# Capstone.net
KiCad netlist of a schematic drawn in EAGLE
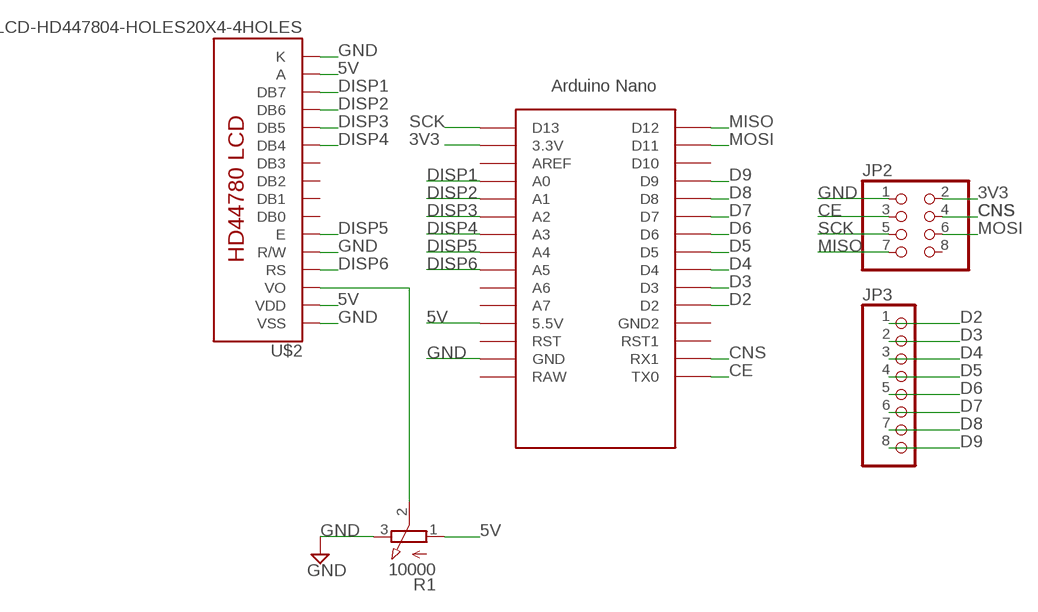
[diagram p0: schematic, sheet 1]

(export (version "E")
  (design (tool "Eeschema 10.0.6"))
  (components
    (comp (ref "JP2")
      (value "PINHD-2X4")
      (footprint "eagle-import:2X04")
      (libsource (lib "eagle-import") (part "PINHD-2X4"))
    )
    (comp (ref "JP3")
      (value "PINHD-1X8")
      (footprint "eagle-import:1X08")
      (libsource (lib "eagle-import") (part "PINHD-1X8"))
    )
    (comp (ref "R1")
      (value "10000")
      (footprint "eagle-import:3RP_1610N")
      (libsource (lib "eagle-import") (part "3RP/1610N"))
    )
    (comp (ref "U$1")
      (value "NANO")
      (footprint "eagle-import:NANO")
      (libsource (lib "eagle-import") (part "NANO"))
    )
    (comp (ref "U$2")
      (value "LCD-HD447804-HOLES20X4-4HOLES")
      (footprint "eagle-import:LCD-20X4-4HOLES")
      (libsource (lib "eagle-import") (part "LCD-HD4478020X4-4HOLES4-HOLES"))
    )
  )
  (nets
    (net (code "1") (name "/3V3") (class "Default")
      (node (ref "JP2") (pin "2") (pinfunction "2_2") (pintype "passive"))
      (node (ref "U$1") (pin "3.3V") (pinfunction "3.3V_3.3V") (pintype "bidirectional"))
    )
    (net (code "2") (name "/5V") (class "Default")
      (node (ref "R1") (pin "1") (pinfunction "A_1") (pintype "passive"))
      (node (ref "U$1") (pin "5V") (pinfunction "5.5V_5V") (pintype "bidirectional"))
      (node (ref "U$2") (pin "P$15") (pinfunction "A_P$15") (pintype "power_in"))
      (node (ref "U$2") (pin "P$2") (pinfunction "VDD_P$2") (pintype "power_in"))
    )
    (net (code "3") (name "/CE") (class "Default")
      (node (ref "JP2") (pin "3") (pinfunction "3_3") (pintype "passive"))
      (node (ref "U$1") (pin "TX0") (pinfunction "TX0_TX0") (pintype "bidirectional"))
    )
    (net (code "4") (name "/CNS") (class "Default")
      (node (ref "JP2") (pin "4") (pinfunction "4_4") (pintype "passive"))
      (node (ref "U$1") (pin "RX1") (pinfunction "RX1_RX1") (pintype "bidirectional"))
    )
    (net (code "5") (name "/D2") (class "Default")
      (node (ref "JP3") (pin "1") (pinfunction "1_1") (pintype "passive"))
      (node (ref "U$1") (pin "D2") (pinfunction "D2_D2") (pintype "bidirectional"))
    )
    (net (code "6") (name "/D3") (class "Default")
      (node (ref "JP3") (pin "2") (pinfunction "2_2") (pintype "passive"))
      (node (ref "U$1") (pin "D3") (pinfunction "D3_D3") (pintype "bidirectional"))
    )
    (net (code "7") (name "/D4") (class "Default")
      (node (ref "JP3") (pin "3") (pinfunction "3_3") (pintype "passive"))
      (node (ref "U$1") (pin "D4") (pinfunction "D4_D4") (pintype "bidirectional"))
    )
    (net (code "8") (name "/D5") (class "Default")
      (node (ref "JP3") (pin "4") (pinfunction "4_4") (pintype "passive"))
      (node (ref "U$1") (pin "D5") (pinfunction "D5_D5") (pintype "bidirectional"))
    )
    (net (code "9") (name "/D6") (class "Default")
      (node (ref "JP3") (pin "5") (pinfunction "5_5") (pintype "passive"))
      (node (ref "U$1") (pin "D6") (pinfunction "D6_D6") (pintype "bidirectional"))
    )
    (net (code "10") (name "/D7") (class "Default")
      (node (ref "JP3") (pin "6") (pinfunction "6_6") (pintype "passive"))
      (node (ref "U$1") (pin "D7") (pinfunction "D7_D7") (pintype "bidirectional"))
    )
    (net (code "11") (name "/D8") (class "Default")
      (node (ref "JP3") (pin "7") (pinfunction "7_7") (pintype "passive"))
      (node (ref "U$1") (pin "D8") (pinfunction "D8_D8") (pintype "bidirectional"))
    )
    (net (code "12") (name "/D9") (class "Default")
      (node (ref "JP3") (pin "8") (pinfunction "8_8") (pintype "passive"))
      (node (ref "U$1") (pin "D9") (pinfunction "D9_D9") (pintype "bidirectional"))
    )
    (net (code "13") (name "/DISP1") (class "Default")
      (node (ref "U$1") (pin "A0") (pinfunction "A0_A0") (pintype "bidirectional"))
      (node (ref "U$2") (pin "P$14") (pinfunction "DB7_P$14") (pintype "bidirectional"))
    )
    (net (code "14") (name "/DISP2") (class "Default")
      (node (ref "U$1") (pin "A1") (pinfunction "A1_A1") (pintype "bidirectional"))
      (node (ref "U$2") (pin "P$13") (pinfunction "DB6_P$13") (pintype "bidirectional"))
    )
    (net (code "15") (name "/DISP3") (class "Default")
      (node (ref "U$1") (pin "A2") (pinfunction "A2_A2") (pintype "bidirectional"))
      (node (ref "U$2") (pin "P$12") (pinfunction "DB5_P$12") (pintype "bidirectional"))
    )
    (net (code "16") (name "/DISP4") (class "Default")
      (node (ref "U$1") (pin "A3") (pinfunction "A3_A3") (pintype "bidirectional"))
      (node (ref "U$2") (pin "P$11") (pinfunction "DB4_P$11") (pintype "bidirectional"))
    )
    (net (code "17") (name "/DISP5") (class "Default")
      (node (ref "U$1") (pin "A4") (pinfunction "A4_A4") (pintype "bidirectional"))
      (node (ref "U$2") (pin "P$6") (pinfunction "E_P$6") (pintype "input"))
    )
    (net (code "18") (name "/DISP6") (class "Default")
      (node (ref "U$1") (pin "A5") (pinfunction "A5_A5") (pintype "bidirectional"))
      (node (ref "U$2") (pin "P$4") (pinfunction "RS_P$4") (pintype "input"))
    )
    (net (code "19") (name "/MISO") (class "Default")
      (node (ref "JP2") (pin "7") (pinfunction "7_7") (pintype "passive"))
      (node (ref "U$1") (pin "D12") (pinfunction "D12_D12") (pintype "bidirectional"))
    )
    (net (code "20") (name "/MOSI") (class "Default")
      (node (ref "JP2") (pin "6") (pinfunction "6_6") (pintype "passive"))
      (node (ref "U$1") (pin "D11") (pinfunction "D11_D11") (pintype "bidirectional"))
    )
    (net (code "21") (name "/SCK") (class "Default")
      (node (ref "JP2") (pin "5") (pinfunction "5_5") (pintype "passive"))
      (node (ref "U$1") (pin "D13") (pinfunction "D13_D13") (pintype "bidirectional"))
    )
    (net (code "22") (name "GND") (class "Default")
      (node (ref "JP2") (pin "1") (pinfunction "1_1") (pintype "passive"))
      (node (ref "R1") (pin "3") (pinfunction "E_3") (pintype "passive"))
      (node (ref "U$1") (pin "GND") (pinfunction "GND_GND") (pintype "bidirectional"))
      (node (ref "U$2") (pin "P$1") (pinfunction "VSS_P$1") (pintype "power_in"))
      (node (ref "U$2") (pin "P$16") (pinfunction "K_P$16") (pintype "power_in"))
      (node (ref "U$2") (pin "P$5") (pinfunction "R/W_P$5") (pintype "input"))
    )
    (net (code "23") (name "Net-(R1-S)") (class "Default")
      (node (ref "R1") (pin "2") (pinfunction "S_2") (pintype "passive"))
      (node (ref "U$2") (pin "P$3") (pinfunction "VO_P$3") (pintype "bidirectional"))
    )
    (net (code "24") (name "unconnected-(JP2-Pad8)") (class "Default")
      (node (ref "JP2") (pin "8") (pinfunction "8_8") (pintype "passive"))
    )
    (net (code "25") (name "unconnected-(U$1-GND2-PadGND1)") (class "Default")
      (node (ref "U$1") (pin "GND1") (pinfunction "GND2_GND1") (pintype "bidirectional"))
    )
    (net (code "26") (name "unconnected-(U$1-PadA6)") (class "Default")
      (node (ref "U$1") (pin "A6") (pinfunction "A6_A6") (pintype "bidirectional"))
    )
    (net (code "27") (name "unconnected-(U$1-PadA7)") (class "Default")
      (node (ref "U$1") (pin "A7") (pinfunction "A7_A7") (pintype "bidirectional"))
    )
    (net (code "28") (name "unconnected-(U$1-PadAREF)") (class "Default")
      (node (ref "U$1") (pin "AREF") (pinfunction "AREF_AREF") (pintype "bidirectional"))
    )
    (net (code "29") (name "unconnected-(U$1-PadD10)") (class "Default")
      (node (ref "U$1") (pin "D10") (pinfunction "D10_D10") (pintype "bidirectional"))
    )
    (net (code "30") (name "unconnected-(U$1-PadICSP1)") (class "Default")
      (node (ref "U$1") (pin "ICSP1") (pinfunction "ICSP1_ICSP1") (pintype "bidirectional"))
    )
    (net (code "31") (name "unconnected-(U$1-PadICSP2)") (class "Default")
      (node (ref "U$1") (pin "ICSP2") (pinfunction "ICSP2_ICSP2") (pintype "bidirectional"))
    )
    (net (code "32") (name "unconnected-(U$1-PadICSP3)") (class "Default")
      (node (ref "U$1") (pin "ICSP3") (pinfunction "ICSP3_ICSP3") (pintype "bidirectional"))
    )
    (net (code "33") (name "unconnected-(U$1-PadICSP4)") (class "Default")
      (node (ref "U$1") (pin "ICSP4") (pinfunction "ICSP4_ICSP4") (pintype "bidirectional"))
    )
    (net (code "34") (name "unconnected-(U$1-PadICSP5)") (class "Default")
      (node (ref "U$1") (pin "ICSP5") (pinfunction "ICSP5_ICSP5") (pintype "bidirectional"))
    )
    (net (code "35") (name "unconnected-(U$1-PadICSP6)") (class "Default")
      (node (ref "U$1") (pin "ICSP6") (pinfunction "ICSP6_ICSP6") (pintype "bidirectional"))
    )
    (net (code "36") (name "unconnected-(U$1-PadRAW)") (class "Default")
      (node (ref "U$1") (pin "RAW") (pinfunction "RAW_RAW") (pintype "bidirectional"))
    )
    (net (code "37") (name "unconnected-(U$1-PadRST)") (class "Default")
      (node (ref "U$1") (pin "RST") (pinfunction "RST_RST") (pintype "bidirectional"))
    )
    (net (code "38") (name "unconnected-(U$1-PadRST1)") (class "Default")
      (node (ref "U$1") (pin "RST1") (pinfunction "RST1_RST1") (pintype "bidirectional"))
    )
    (net (code "39") (name "unconnected-(U$2-DB0-PadP$7)") (class "Default")
      (node (ref "U$2") (pin "P$7") (pinfunction "DB0_P$7") (pintype "bidirectional"))
    )
    (net (code "40") (name "unconnected-(U$2-DB1-PadP$8)") (class "Default")
      (node (ref "U$2") (pin "P$8") (pinfunction "DB1_P$8") (pintype "bidirectional"))
    )
    (net (code "41") (name "unconnected-(U$2-DB2-PadP$9)") (class "Default")
      (node (ref "U$2") (pin "P$9") (pinfunction "DB2_P$9") (pintype "bidirectional"))
    )
    (net (code "42") (name "unconnected-(U$2-DB3-PadP$10)") (class "Default")
      (node (ref "U$2") (pin "P$10") (pinfunction "DB3_P$10") (pintype "bidirectional"))
    )
  )
)
